# analog-noise-fob-sp23.net
KiCad netlist of a schematic drawn in EAGLE
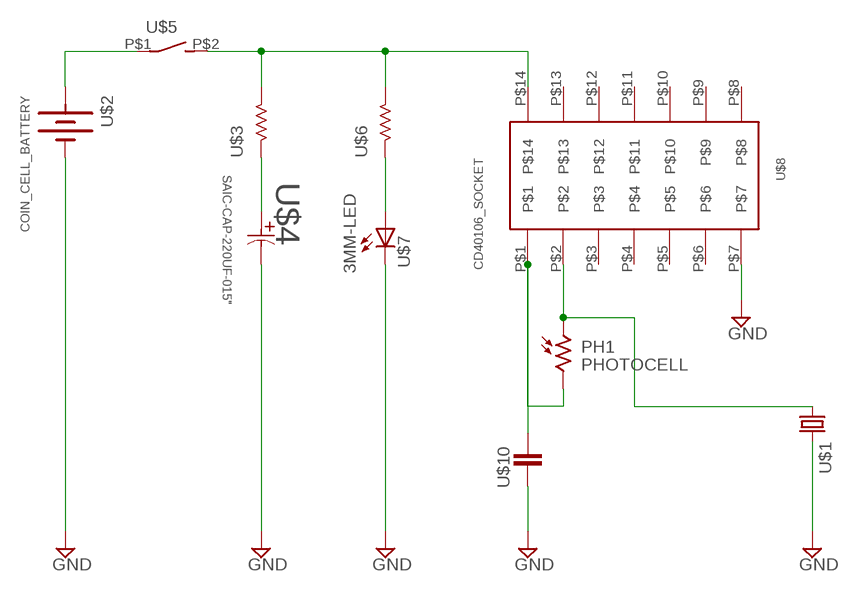
[diagram p0: schematic, sheet 1]

(export (version "E")
  (design (tool "Eeschema 10.0.6"))
  (components
    (comp (ref "PH1")
      (value "PHOTOCELL")
      (footprint "eagle-import:PHOTOCELL")
      (libsource (lib "eagle-import") (part "PHOTOCELL"))
    )
    (comp (ref "U$1")
      (value "PIEZO_BUZZER_2")
      (footprint "eagle-import:PIEZO_BUZZER_2")
      (libsource (lib "eagle-import") (part "PIEZO_BUZZER_2"))
    )
    (comp (ref "U$2")
      (value "COIN_CELL_BATTERY")
      (footprint "eagle-import:COIN_BATTERY")
      (libsource (lib "eagle-import") (part "COIN_CELL_BATTERY"))
    )
    (comp (ref "U$3")
      (value "RESISTOR-1/4W-THROUGH-HOLE")
      (footprint "eagle-import:1_4W_TH_RESISTOR")
      (libsource (lib "eagle-import") (part "RESISTOR-1/4W-THROUGH-HOLE"))
    )
    (comp (ref "U$4")
      (value "SAIC-CAP-220UF-015\"")
      (footprint "eagle-import:SAIC-CAP-0.15_-LEAD-SPACING-01")
      (libsource (lib "eagle-import") (part "SAIC-CAP-220UF-015{dblquote}"))
    )
    (comp (ref "U$5")
      (value "TACTILE_SWITCH")
      (footprint "eagle-import:TACTILE_SWITCH")
      (libsource (lib "eagle-import") (part "TACTILE_SWITCH"))
    )
    (comp (ref "U$6")
      (value "RESISTOR-1/4W-THROUGH-HOLE")
      (footprint "eagle-import:1_4W_TH_RESISTOR")
      (libsource (lib "eagle-import") (part "RESISTOR-1/4W-THROUGH-HOLE"))
    )
    (comp (ref "U$7")
      (value "3MM-LED")
      (footprint "eagle-import:LED3MM")
      (libsource (lib "eagle-import") (part "3MM-LED"))
    )
    (comp (ref "U$8")
      (value "CD40106_SOCKET")
      (footprint "eagle-import:DIP_14_SOCKET")
      (libsource (lib "eagle-import") (part "CD40106_SOCKET"))
    )
    (comp (ref "U$10")
      (value "SAIC-CAP-0.1UF-02\"")
      (footprint "eagle-import:SAIC-CAP-0.2_-LEAD-SPACING-03")
      (libsource (lib "eagle-import") (part "SAIC-CAP-0.1UF-02{dblquote}"))
    )
  )
  (nets
    (net (code "1") (name "GND") (class "Default")
      (node (ref "U$1") (pin "P$2") (pinfunction "2_P$2") (pintype "passive"))
      (node (ref "U$10") (pin "P$1") (pinfunction "1_P$1") (pintype "passive"))
      (node (ref "U$2") (pin "P$2") (pinfunction "-_P$2") (pintype "power_in"))
      (node (ref "U$4") (pin "P$2") (pinfunction "22_P$2") (pintype "passive"))
      (node (ref "U$7") (pin "K") (pinfunction "2_K") (pintype "output"))
      (node (ref "U$8") (pin "P$7") (pinfunction "P$7_P$7") (pintype "bidirectional"))
    )
    (net (code "2") (name "Net-(PH1-1)") (class "Default")
      (node (ref "PH1") (pin "P$1") (pinfunction "1_P$1") (pintype "passive"))
      (node (ref "U$1") (pin "P$1") (pinfunction "1_P$1") (pintype "passive"))
      (node (ref "U$8") (pin "P$2") (pinfunction "P$2_P$2") (pintype "bidirectional"))
    )
    (net (code "3") (name "Net-(PH1-2)") (class "Default")
      (node (ref "PH1") (pin "P$2") (pinfunction "2_P$2") (pintype "passive"))
      (node (ref "U$10") (pin "P$2") (pinfunction "2_P$2") (pintype "passive"))
      (node (ref "U$8") (pin "P$1") (pinfunction "P$1_P$1") (pintype "bidirectional"))
    )
    (net (code "4") (name "Net-(U$2-+)") (class "Default")
      (node (ref "U$2") (pin "P$1") (pinfunction "+_P$1") (pintype "power_in"))
      (node (ref "U$5") (pin "P$1") (pinfunction "P_P$1") (pintype "passive"))
    )
    (net (code "5") (name "Net-(U$4-11)") (class "Default")
      (node (ref "U$3") (pin "P$1") (pinfunction "P$1_P$1") (pintype "bidirectional"))
      (node (ref "U$4") (pin "P$1") (pinfunction "11_P$1") (pintype "passive"))
    )
    (net (code "6") (name "Net-(U$5-S)") (class "Default")
      (node (ref "U$3") (pin "P$2") (pinfunction "P$2_P$2") (pintype "bidirectional"))
      (node (ref "U$5") (pin "P$2") (pinfunction "S_P$2") (pintype "passive"))
      (node (ref "U$6") (pin "P$2") (pinfunction "P$2_P$2") (pintype "bidirectional"))
      (node (ref "U$8") (pin "P$14") (pinfunction "P$14_P$14") (pintype "bidirectional"))
    )
    (net (code "7") (name "Net-(U$7-1)") (class "Default")
      (node (ref "U$6") (pin "P$1") (pinfunction "P$1_P$1") (pintype "bidirectional"))
      (node (ref "U$7") (pin "A") (pinfunction "1_A") (pintype "input"))
    )
    (net (code "8") (name "unconnected-(U$8-PadP$3)") (class "Default")
      (node (ref "U$8") (pin "P$3") (pinfunction "P$3_P$3") (pintype "bidirectional"))
    )
    (net (code "9") (name "unconnected-(U$8-PadP$4)") (class "Default")
      (node (ref "U$8") (pin "P$4") (pinfunction "P$4_P$4") (pintype "bidirectional"))
    )
    (net (code "10") (name "unconnected-(U$8-PadP$5)") (class "Default")
      (node (ref "U$8") (pin "P$5") (pinfunction "P$5_P$5") (pintype "bidirectional"))
    )
    (net (code "11") (name "unconnected-(U$8-PadP$6)") (class "Default")
      (node (ref "U$8") (pin "P$6") (pinfunction "P$6_P$6") (pintype "bidirectional"))
    )
    (net (code "12") (name "unconnected-(U$8-PadP$8)") (class "Default")
      (node (ref "U$8") (pin "P$8") (pinfunction "P$8_P$8") (pintype "bidirectional"))
    )
    (net (code "13") (name "unconnected-(U$8-PadP$9)") (class "Default")
      (node (ref "U$8") (pin "P$9") (pinfunction "P$9_P$9") (pintype "bidirectional"))
    )
    (net (code "14") (name "unconnected-(U$8-PadP$10)") (class "Default")
      (node (ref "U$8") (pin "P$10") (pinfunction "P$10_P$10") (pintype "bidirectional"))
    )
    (net (code "15") (name "unconnected-(U$8-PadP$11)") (class "Default")
      (node (ref "U$8") (pin "P$11") (pinfunction "P$11_P$11") (pintype "bidirectional"))
    )
    (net (code "16") (name "unconnected-(U$8-PadP$12)") (class "Default")
      (node (ref "U$8") (pin "P$12") (pinfunction "P$12_P$12") (pintype "bidirectional"))
    )
    (net (code "17") (name "unconnected-(U$8-PadP$13)") (class "Default")
      (node (ref "U$8") (pin "P$13") (pinfunction "P$13_P$13") (pintype "bidirectional"))
    )
  )
)
